# GRHV_Double_25v_KC_T.net
KiCad netlist of a schematic drawn in Altium Designer
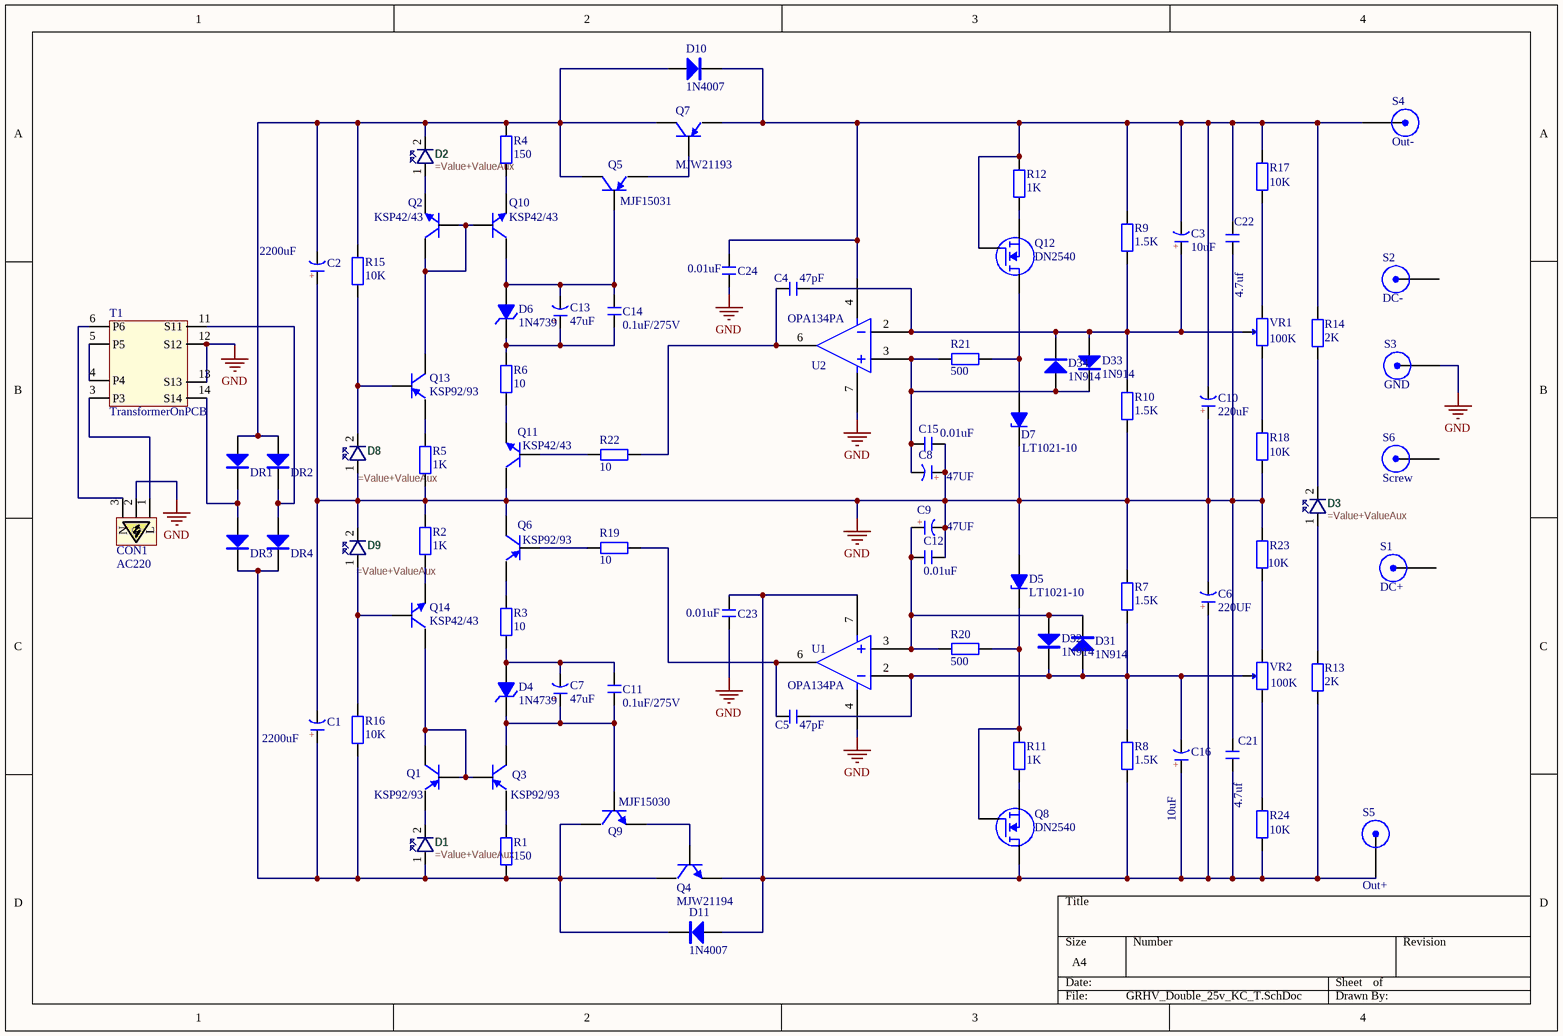
[diagram p0: GRHV_Double_25v_KC_T.SchDoc]

(export (version "E")
  (design (tool "Eeschema 10.0.6"))
  (components
    (comp (ref "C1")
      (value "2200uF")
      (footprint "CAP 11*35*60")
      (description "直插电解电容")
      (fields (field (name "版权归属") "源创客"))
      (libsource (lib "") (part "C-CAP_1"))
    )
    (comp (ref "C2")
      (value "2200uF")
      (footprint "CAP 11*35*60")
      (description "直插电解电容")
      (fields (field (name "版权归属") "源创客"))
      (libsource (lib "") (part "C-CAP_1"))
    )
    (comp (ref "C3")
      (value "10uF")
      (footprint "CAP 7.0*16.5*20")
      (description "直插电解电容")
      (fields (field (name "版权归属") "源创客"))
      (libsource (lib "") (part "C-CAP_1"))
    )
    (comp (ref "C4")
      (value "47pF")
      (footprint "CBB 6.3*6.3*5")
      (description "CBB电容")
      (fields (field (name "版权归属") "源创客"))
      (libsource (lib "电阻-电容-电感") (part "C-CBB"))
    )
    (comp (ref "C5")
      (value "47pF")
      (footprint "CBB 6.3*6.3*5")
      (description "CBB电容")
      (fields (field (name "版权归属") "源创客"))
      (libsource (lib "电阻-电容-电感") (part "C-CBB"))
    )
    (comp (ref "C6")
      (value "220UF")
      (footprint "CAP 7.0*16.5*20")
      (description "直插电解电容")
      (fields (field (name "版权归属") "源创客"))
      (libsource (lib "") (part "C-CAP_1"))
    )
    (comp (ref "C7")
      (value "47uF")
      (footprint "CAP 2.5*6.3*11.2")
      (description "直插电解电容")
      (fields (field (name "版权归属") "源创客"))
      (libsource (lib "") (part "C-CAP_1"))
    )
    (comp (ref "C8")
      (value "47UF")
      (footprint "CAP 2.5*6.3*11.2")
      (description "直插电解电容")
      (fields (field (name "版权归属") "源创客"))
      (libsource (lib "电阻-电容-电感") (part "C-CAP"))
    )
    (comp (ref "C9")
      (value "47UF")
      (footprint "CAP 2.5*6.3*11.2")
      (description "直插电解电容")
      (fields (field (name "版权归属") "源创客"))
      (libsource (lib "电阻-电容-电感") (part "C-CAP"))
    )
    (comp (ref "C10")
      (value "220uF")
      (footprint "CAP 7.0*16.5*20")
      (description "直插电解电容")
      (fields (field (name "版权归属") "源创客"))
      (libsource (lib "") (part "C-CAP_1"))
    )
    (comp (ref "C11")
      (value "0.1uF/275V")
      (footprint "CBB 6.3*6.3*5")
      (description "CBB电容")
      (fields (field (name "版权归属") "源创客"))
      (libsource (lib "电阻-电容-电感") (part "C-CBB"))
    )
    (comp (ref "C12")
      (value "0.01uF")
      (footprint "CBB 6.3*6.3*5")
      (description "CBB电容")
      (fields (field (name "版权归属") "源创客"))
      (libsource (lib "电阻-电容-电感") (part "C-CBB"))
    )
    (comp (ref "C13")
      (value "47uF")
      (footprint "CAP 2.5*6.3*11.2")
      (description "直插电解电容")
      (fields (field (name "版权归属") "源创客"))
      (libsource (lib "") (part "C-CAP_1"))
    )
    (comp (ref "C14")
      (value "0.1uF/275V")
      (footprint "CBB 6.3*6.3*5")
      (description "CBB电容")
      (fields (field (name "版权归属") "源创客"))
      (libsource (lib "电阻-电容-电感") (part "C-CBB"))
    )
    (comp (ref "C15")
      (value "0.01uF")
      (footprint "CBB 6.3*6.3*5")
      (description "CBB电容")
      (fields (field (name "版权归属") "源创客"))
      (libsource (lib "电阻-电容-电感") (part "C-CBB"))
    )
    (comp (ref "C16")
      (value "10uF")
      (footprint "CAP 7.0*16.5*20")
      (description "直插电解电容")
      (fields (field (name "版权归属") "源创客"))
      (libsource (lib "") (part "C-CAP_1"))
    )
    (comp (ref "C21")
      (value "4.7uf")
      (footprint "CBB 7.2*7.2*13")
      (description "MKS薄膜电容")
      (libsource (lib "电阻-电容-电感") (part "C-MKS"))
    )
    (comp (ref "C22")
      (value "4.7uf")
      (footprint "CBB 7.2*7.2*13")
      (description "MKS薄膜电容")
      (libsource (lib "电阻-电容-电感") (part "C-MKS"))
    )
    (comp (ref "C23")
      (value "0.01uF")
      (footprint "CBB 6.3*6.3*5")
      (description "CBB电容")
      (fields (field (name "版权归属") "源创客"))
      (libsource (lib "电阻-电容-电感") (part "C-CBB"))
    )
    (comp (ref "C24")
      (value "0.01uF")
      (footprint "CBB 6.3*6.3*5")
      (description "CBB电容")
      (fields (field (name "版权归属") "源创客"))
      (libsource (lib "电阻-电容-电感") (part "C-CBB"))
    )
    (comp (ref "CON1")
      (value "AC220")
      (footprint "HX5.08-3L")
      (libsource (lib "Connectors") (part "AC220-3"))
    )
    (comp (ref "D1")
      (value "~")
      (footprint "LED 3MM-R")
      (description "直插式LED")
      (libsource (lib "LED") (part "LED"))
    )
    (comp (ref "D2")
      (value "~")
      (footprint "LED 3MM-R")
      (description "直插式LED")
      (libsource (lib "LED") (part "LED"))
    )
    (comp (ref "D3")
      (value "~")
      (footprint "LED 3MM-R")
      (description "直插式LED")
      (libsource (lib "LED") (part "LED"))
    )
    (comp (ref "D4")
      (value "1N4739")
      (footprint "DO-41")
      (description "9.1V/1W稳压管")
      (libsource (lib "二极管-整流桥") (part "1N4739"))
    )
    (comp (ref "D5")
      (value "LT1021-10")
      (footprint "DIP8-300_MH")
      (description "10V Precision Reference 2 Pin Config")
      (libsource (lib "电压参考") (part "LT1021-10-2P"))
    )
    (comp (ref "D6")
      (value "1N4739")
      (footprint "DO-41")
      (description "9.1V/1W稳压管")
      (libsource (lib "二极管-整流桥") (part "1N4739"))
    )
    (comp (ref "D7")
      (value "LT1021-10")
      (footprint "DIP8-300_MH")
      (description "10V Precision Reference 2 Pin Config")
      (libsource (lib "电压参考") (part "LT1021-10-2P"))
    )
    (comp (ref "D8")
      (value "~")
      (footprint "LED 3MM-R")
      (description "直插式LED")
      (libsource (lib "LED") (part "LED"))
    )
    (comp (ref "D9")
      (value "~")
      (footprint "LED 3MM-R")
      (description "直插式LED")
      (libsource (lib "LED") (part "LED"))
    )
    (comp (ref "D10")
      (value "1N4007")
      (footprint "DO-41")
      (description "整流二极管")
      (fields (field (name "版权归属") "源创客"))
      (libsource (lib "二极管-整流桥") (part "1N4007"))
    )
    (comp (ref "D11")
      (value "1N4007")
      (footprint "DO-41")
      (description "整流二极管")
      (fields (field (name "版权归属") "源创客"))
      (libsource (lib "二极管-整流桥") (part "1N4007"))
    )
    (comp (ref "D31")
      (value "1N914")
      (footprint "DO-35")
      (description "高速开关管 1V/0.25W")
      (libsource (lib "二极管-整流桥") (part "1N914"))
    )
    (comp (ref "D32")
      (value "1N914")
      (footprint "DO-35")
      (description "高速开关管 1V/0.25W")
      (libsource (lib "二极管-整流桥") (part "1N914"))
    )
    (comp (ref "D33")
      (value "1N914")
      (footprint "DO-35")
      (description "高速开关管 1V/0.25W")
      (libsource (lib "二极管-整流桥") (part "1N914"))
    )
    (comp (ref "D34")
      (value "1N914")
      (footprint "DO-35")
      (description "高速开关管 1V/0.25W")
      (libsource (lib "二极管-整流桥") (part "1N914"))
    )
    (comp (ref "DR1")
      (value "VS-HFA08TB60-M3")
      (footprint "TO220AC")
      (description "Ultrafast Soft Recovery Diado 8A 600V")
      (libsource (lib "二极管-整流桥") (part "VS-HFA08TB60-M3"))
    )
    (comp (ref "DR2")
      (value "VS-HFA08TB60-M3")
      (footprint "TO220AC")
      (description "Ultrafast Soft Recovery Diado 8A 600V")
      (libsource (lib "二极管-整流桥") (part "VS-HFA08TB60-M3"))
    )
    (comp (ref "DR3")
      (value "VS-HFA08TB60-M3")
      (footprint "TO220AC")
      (description "Ultrafast Soft Recovery Diado 8A 600V")
      (libsource (lib "二极管-整流桥") (part "VS-HFA08TB60-M3"))
    )
    (comp (ref "DR4")
      (value "VS-HFA08TB60-M3")
      (footprint "TO220AC")
      (description "Ultrafast Soft Recovery Diado 8A 600V")
      (libsource (lib "二极管-整流桥") (part "VS-HFA08TB60-M3"))
    )
    (comp (ref "Q1")
      (value "KSP92/93")
      (footprint "TO92A")
      (description "High Voltage PNP Transistor")
      (libsource (lib "三极管") (part "KSP92/93"))
    )
    (comp (ref "Q2")
      (value "KSP42/43")
      (footprint "TO92A")
      (description "High Voltage NPN Transistor")
      (libsource (lib "三极管") (part "KSP42/43"))
    )
    (comp (ref "Q3")
      (value "KSP92/93")
      (footprint "TO92A")
      (description "High Voltage PNP Transistor")
      (libsource (lib "三极管") (part "KSP92/93"))
    )
    (comp (ref "Q4")
      (value "MJW21194")
      (footprint "TO247V-HeatSink")
      (description "Power NPN Transistor")
      (libsource (lib "三极管") (part "MJW21194"))
    )
    (comp (ref "Q5")
      (value "MJF15031")
      (footprint "TO220V")
      (description "Power PNP Transistor")
      (libsource (lib "三极管") (part "MJF15031"))
    )
    (comp (ref "Q6")
      (value "KSP92/93")
      (footprint "TO92A")
      (description "High Voltage PNP Transistor")
      (libsource (lib "三极管") (part "KSP92/93"))
    )
    (comp (ref "Q7")
      (value "MJW21193")
      (footprint "TO247V-HeatSink")
      (description "Power PNP Transistor")
      (libsource (lib "三极管") (part "MJW21193"))
    )
    (comp (ref "Q8")
      (value "DN2540")
      (footprint "TO92A")
      (description "N沟道耗尽型DMOS场效应管 400V/150ma")
      (libsource (lib "场效应管") (part "DN2540"))
    )
    (comp (ref "Q9")
      (value "MJF15030")
      (footprint "TO220V")
      (description "Power NPN Transistor")
      (libsource (lib "三极管") (part "MJF15030"))
    )
    (comp (ref "Q10")
      (value "KSP42/43")
      (footprint "TO92A")
      (description "High Voltage NPN Transistor")
      (libsource (lib "三极管") (part "KSP42/43"))
    )
    (comp (ref "Q11")
      (value "KSP42/43")
      (footprint "TO92A")
      (description "High Voltage NPN Transistor")
      (libsource (lib "三极管") (part "KSP42/43"))
    )
    (comp (ref "Q12")
      (value "DN2540")
      (footprint "TO92A")
      (description "N沟道耗尽型DMOS场效应管 400V/150ma")
      (libsource (lib "场效应管") (part "DN2540"))
    )
    (comp (ref "Q13")
      (value "KSP92/93")
      (footprint "TO92A")
      (description "High Voltage PNP Transistor")
      (libsource (lib "三极管") (part "KSP92/93"))
    )
    (comp (ref "Q14")
      (value "KSP42/43")
      (footprint "TO92A")
      (description "High Voltage NPN Transistor")
      (libsource (lib "三极管") (part "KSP42/43"))
    )
    (comp (ref "R1")
      (value "150")
      (footprint "RS 1/4W")
      (description "直插色环电阻")
      (fields (field (name "版权归属") "源创客"))
      (libsource (lib "电阻-电容-电感") (part "R-CRR"))
    )
    (comp (ref "R2")
      (value "1K")
      (footprint "RS 1/4W")
      (description "直插色环电阻")
      (fields (field (name "版权归属") "源创客"))
      (libsource (lib "电阻-电容-电感") (part "R-CRR"))
    )
    (comp (ref "R3")
      (value "10")
      (footprint "RS 1/4W")
      (description "直插色环电阻")
      (fields (field (name "版权归属") "源创客"))
      (libsource (lib "电阻-电容-电感") (part "R-CRR"))
    )
    (comp (ref "R4")
      (value "150")
      (footprint "RS 1/4W")
      (description "直插色环电阻")
      (fields (field (name "版权归属") "源创客"))
      (libsource (lib "电阻-电容-电感") (part "R-CRR"))
    )
    (comp (ref "R5")
      (value "1K")
      (footprint "RS 1/4W")
      (description "直插色环电阻")
      (fields (field (name "版权归属") "源创客"))
      (libsource (lib "电阻-电容-电感") (part "R-CRR"))
    )
    (comp (ref "R6")
      (value "10")
      (footprint "RS 1/4W")
      (description "直插色环电阻")
      (fields (field (name "版权归属") "源创客"))
      (libsource (lib "电阻-电容-电感") (part "R-CRR"))
    )
    (comp (ref "R7")
      (value "1.5K")
      (footprint "RS 1/4W")
      (description "直插色环电阻")
      (fields (field (name "版权归属") "源创客"))
      (libsource (lib "电阻-电容-电感") (part "R-CRR"))
    )
    (comp (ref "R8")
      (value "1.5K")
      (footprint "RS 1/4W")
      (description "直插色环电阻")
      (fields (field (name "版权归属") "源创客"))
      (libsource (lib "电阻-电容-电感") (part "R-CRR"))
    )
    (comp (ref "R9")
      (value "1.5K")
      (footprint "RS 1/4W")
      (description "直插色环电阻")
      (fields (field (name "版权归属") "源创客"))
      (libsource (lib "电阻-电容-电感") (part "R-CRR"))
    )
    (comp (ref "R10")
      (value "1.5K")
      (footprint "RS 1/4W")
      (description "直插色环电阻")
      (fields (field (name "版权归属") "源创客"))
      (libsource (lib "电阻-电容-电感") (part "R-CRR"))
    )
    (comp (ref "R11")
      (value "1K")
      (footprint "RS 1/4W-V3")
      (description "直插色环电阻")
      (fields (field (name "版权归属") "源创客"))
      (libsource (lib "电阻-电容-电感") (part "R-CRR"))
    )
    (comp (ref "R12")
      (value "1K")
      (footprint "RS 1/4W-V3")
      (description "直插色环电阻")
      (fields (field (name "版权归属") "源创客"))
      (libsource (lib "电阻-电容-电感") (part "R-CRR"))
    )
    (comp (ref "R13")
      (value "2K")
      (footprint "RS 1/4W")
      (description "直插色环电阻")
      (fields (field (name "版权归属") "源创客"))
      (libsource (lib "电阻-电容-电感") (part "R-CRR"))
    )
    (comp (ref "R14")
      (value "2K")
      (footprint "RS 1/4W")
      (description "直插色环电阻")
      (fields (field (name "版权归属") "源创客"))
      (libsource (lib "电阻-电容-电感") (part "R-CRR"))
    )
    (comp (ref "R15")
      (value "10K")
      (footprint "RS 1/4W")
      (description "直插色环电阻")
      (fields (field (name "版权归属") "源创客"))
      (libsource (lib "电阻-电容-电感") (part "R-CRR"))
    )
    (comp (ref "R16")
      (value "10K")
      (footprint "RS 1/4W")
      (description "直插色环电阻")
      (fields (field (name "版权归属") "源创客"))
      (libsource (lib "电阻-电容-电感") (part "R-CRR"))
    )
    (comp (ref "R17")
      (value "10K")
      (footprint "RS 1/4W-V3")
      (description "直插色环电阻")
      (fields (field (name "版权归属") "源创客"))
      (libsource (lib "电阻-电容-电感") (part "R-CRR"))
    )
    (comp (ref "R18")
      (value "10K")
      (footprint "RS 1/4W")
      (description "直插色环电阻")
      (fields (field (name "版权归属") "源创客"))
      (libsource (lib "电阻-电容-电感") (part "R-CRR"))
    )
    (comp (ref "R19")
      (value "10")
      (footprint "RS 1/4W")
      (description "直插色环电阻")
      (fields (field (name "版权归属") "源创客"))
      (libsource (lib "电阻-电容-电感") (part "R-CRR"))
    )
    (comp (ref "R20")
      (value "500")
      (footprint "RS 1/4W-V3")
      (description "直插色环电阻")
      (fields (field (name "版权归属") "源创客"))
      (libsource (lib "电阻-电容-电感") (part "R-CRR"))
    )
    (comp (ref "R21")
      (value "500")
      (footprint "RS 1/4W-V3")
      (description "直插色环电阻")
      (fields (field (name "版权归属") "源创客"))
      (libsource (lib "电阻-电容-电感") (part "R-CRR"))
    )
    (comp (ref "R22")
      (value "10")
      (footprint "RS 1/4W")
      (description "直插色环电阻")
      (fields (field (name "版权归属") "源创客"))
      (libsource (lib "电阻-电容-电感") (part "R-CRR"))
    )
    (comp (ref "R23")
      (value "10K")
      (footprint "RS 1/4W")
      (description "直插色环电阻")
      (fields (field (name "版权归属") "源创客"))
      (libsource (lib "电阻-电容-电感") (part "R-CRR"))
    )
    (comp (ref "R24")
      (value "10K")
      (footprint "RS 1/4W-V3")
      (description "直插色环电阻")
      (fields (field (name "版权归属") "源创客"))
      (libsource (lib "电阻-电容-电感") (part "R-CRR"))
    )
    (comp (ref "S1")
      (value "DC+")
      (footprint "Screw-M3")
      (description "Screw Connector")
      (libsource (lib "Connectors") (part "ScrewConnector"))
    )
    (comp (ref "S2")
      (value "DC-")
      (footprint "Screw-M3")
      (description "Screw Connector")
      (libsource (lib "Connectors") (part "ScrewConnector"))
    )
    (comp (ref "S3")
      (value "GND")
      (footprint "Screw-M4-Small")
      (description "Screw Connector")
      (libsource (lib "Connectors") (part "ScrewConnector"))
    )
    (comp (ref "S4")
      (value "Out-")
      (footprint "Screw-M4-Small")
      (description "Screw Connector")
      (libsource (lib "Connectors") (part "ScrewConnector"))
    )
    (comp (ref "S5")
      (value "Out+")
      (footprint "Screw-M4-Small")
      (description "Screw Connector")
      (libsource (lib "Connectors") (part "ScrewConnector"))
    )
    (comp (ref "S6")
      (value "Screw")
      (footprint "Screw-M3")
      (description "Screw Connector")
      (libsource (lib "Connectors") (part "ScrewConnector"))
    )
    (comp (ref "T1")
      (value "TransformerOnPCB")
      (footprint "TalemaTransformer25W")
      (description "Talema On Board Transformer 25W")
      (libsource (lib "KC_amp") (part "TransformerOnPCB"))
    )
    (comp (ref "U1") (value "OPA134PA") (footprint "DIP8-300_MH") (libsource (lib "运放") (part "OPA134PA")))
    (comp (ref "U2") (value "OPA134PA") (footprint "DIP8-300_MH") (libsource (lib "运放") (part "OPA134PA")))
    (comp (ref "VR1")
      (value "100K")
      (footprint "RS 1/2W-VR")
      (description "直插可调电阻-顶调")
      (fields (field (name "Comment") "VR-W"))
      (libsource (lib "电阻-电容-电感") (part "VR-W"))
    )
    (comp (ref "VR2")
      (value "100K")
      (footprint "RS 1/2W-VR")
      (description "直插可调电阻-顶调")
      (fields (field (name "Comment") "VR-W"))
      (libsource (lib "电阻-电容-电感") (part "VR-W"))
    )
  )
  (nets
    (net (code "1") (name "GND") (class "Default")
      (node (ref "C1") (pin "2") (pinfunction "K_2") (pintype "passive"))
      (node (ref "C10") (pin "1") (pinfunction "A_1") (pintype "passive"))
      (node (ref "C12") (pin "2") (pinfunction "2_2") (pintype "passive"))
      (node (ref "C15") (pin "2") (pinfunction "2_2") (pintype "passive"))
      (node (ref "C2") (pin "1") (pinfunction "A_1") (pintype "passive"))
      (node (ref "C21") (pin "2") (pinfunction "2_2") (pintype "passive"))
      (node (ref "C22") (pin "1") (pinfunction "1_1") (pintype "passive"))
      (node (ref "C23") (pin "1") (pinfunction "1_1") (pintype "passive"))
      (node (ref "C24") (pin "1") (pinfunction "1_1") (pintype "passive"))
      (node (ref "C6") (pin "2") (pinfunction "K_2") (pintype "passive"))
      (node (ref "C8") (pin "1") (pinfunction "A_1") (pintype "passive"))
      (node (ref "C9") (pin "2") (pinfunction "K_2") (pintype "passive"))
      (node (ref "CON1") (pin "2") (pinfunction "G_2") (pintype "passive"))
      (node (ref "D5") (pin "4") (pinfunction "A_4") (pintype "passive"))
      (node (ref "D7") (pin "6") (pinfunction "K_6") (pintype "passive"))
      (node (ref "D8") (pin "1") (pinfunction "A_1") (pintype "passive"))
      (node (ref "D9") (pin "2") (pinfunction "K_2") (pintype "passive"))
      (node (ref "Q11") (pin "3") (pinfunction "C_3") (pintype "passive"))
      (node (ref "Q6") (pin "3") (pinfunction "C_3") (pintype "passive"))
      (node (ref "R10") (pin "1") (pinfunction "1_1") (pintype "passive"))
      (node (ref "R18") (pin "1") (pinfunction "1_1") (pintype "passive"))
      (node (ref "R2") (pin "2") (pinfunction "2_2") (pintype "passive"))
      (node (ref "R23") (pin "2") (pinfunction "2_2") (pintype "passive"))
      (node (ref "R5") (pin "1") (pinfunction "1_1") (pintype "passive"))
      (node (ref "R7") (pin "2") (pinfunction "2_2") (pintype "passive"))
      (node (ref "S3") (pin "1") (pinfunction "X_1") (pintype "passive"))
      (node (ref "T1") (pin "12") (pinfunction "S12_12") (pintype "passive"))
      (node (ref "T1") (pin "13") (pinfunction "S13_13") (pintype "passive"))
      (node (ref "U1") (pin "4") (pinfunction "V-_4") (pintype "passive"))
      (node (ref "U2") (pin "7") (pinfunction "V+_7") (pintype "passive"))
    )
    (net (code "2") (name "Net-(C1-A)") (class "Default")
      (node (ref "C1") (pin "1") (pinfunction "A_1") (pintype "passive"))
      (node (ref "D1") (pin "1") (pinfunction "A_1") (pintype "passive"))
      (node (ref "D11") (pin "2") (pinfunction "K_2") (pintype "passive"))
      (node (ref "DR3") (pin "1") (pinfunction "Cathode_1") (pintype "passive"))
      (node (ref "DR4") (pin "1") (pinfunction "Cathode_1") (pintype "passive"))
      (node (ref "Q4") (pin "2") (pinfunction "C_2") (pintype "passive"))
      (node (ref "Q9") (pin "2") (pinfunction "C_2") (pintype "passive"))
      (node (ref "R1") (pin "1") (pinfunction "1_1") (pintype "passive"))
      (node (ref "R16") (pin "1") (pinfunction "1_1") (pintype "passive"))
    )
    (net (code "3") (name "Net-(C2-K)") (class "Default")
      (node (ref "C2") (pin "2") (pinfunction "K_2") (pintype "passive"))
      (node (ref "D10") (pin "1") (pinfunction "A_1") (pintype "passive"))
      (node (ref "D2") (pin "2") (pinfunction "K_2") (pintype "passive"))
      (node (ref "DR1") (pin "2") (pinfunction "Anode_2") (pintype "passive"))
      (node (ref "DR2") (pin "2") (pinfunction "Anode_2") (pintype "passive"))
      (node (ref "Q5") (pin "2") (pinfunction "C_2") (pintype "passive"))
      (node (ref "Q7") (pin "2") (pinfunction "C_2") (pintype "passive"))
      (node (ref "R15") (pin "2") (pinfunction "2_2") (pintype "passive"))
      (node (ref "R4") (pin "2") (pinfunction "2_2") (pintype "passive"))
    )
    (net (code "4") (name "Net-(C3-A)") (class "Default")
      (node (ref "C3") (pin "1") (pinfunction "A_1") (pintype "passive"))
      (node (ref "C4") (pin "2") (pinfunction "2_2") (pintype "passive"))
      (node (ref "D33") (pin "1") (pinfunction "A_1") (pintype "passive"))
      (node (ref "D34") (pin "2") (pinfunction "K_2") (pintype "passive"))
      (node (ref "R10") (pin "2") (pinfunction "2_2") (pintype "passive"))
      (node (ref "R9") (pin "1") (pinfunction "1_1") (pintype "passive"))
      (node (ref "U2") (pin "2") (pinfunction "-in_2") (pintype "passive"))
      (node (ref "VR1") (pin "3") (pinfunction "3_3") (pintype "passive"))
    )
    (net (code "5") (name "Net-(C7-A)") (class "Default")
      (node (ref "C11") (pin "1") (pinfunction "1_1") (pintype "passive"))
      (node (ref "C7") (pin "1") (pinfunction "A_1") (pintype "passive"))
      (node (ref "D4") (pin "2") (pinfunction "K_2") (pintype "passive"))
      (node (ref "Q3") (pin "3") (pinfunction "C_3") (pintype "passive"))
      (node (ref "Q9") (pin "1") (pinfunction "B_1") (pintype "passive"))
    )
    (net (code "6") (name "Net-(C7-K)") (class "Default")
      (node (ref "C11") (pin "2") (pinfunction "2_2") (pintype "passive"))
      (node (ref "C7") (pin "2") (pinfunction "K_2") (pintype "passive"))
      (node (ref "D4") (pin "1") (pinfunction "A_1") (pintype "passive"))
      (node (ref "R3") (pin "1") (pinfunction "1_1") (pintype "passive"))
    )
    (net (code "7") (name "Net-(C8-K)") (class "Default")
      (node (ref "C15") (pin "1") (pinfunction "1_1") (pintype "passive"))
      (node (ref "C8") (pin "2") (pinfunction "K_2") (pintype "passive"))
      (node (ref "D33") (pin "2") (pinfunction "K_2") (pintype "passive"))
      (node (ref "D34") (pin "1") (pinfunction "A_1") (pintype "passive"))
      (node (ref "R21") (pin "1") (pinfunction "1_1") (pintype "passive"))
      (node (ref "U2") (pin "3") (pinfunction "+in_3") (pintype "passive"))
    )
    (net (code "8") (name "Net-(C9-A)") (class "Default")
      (node (ref "C12") (pin "1") (pinfunction "1_1") (pintype "passive"))
      (node (ref "C9") (pin "1") (pinfunction "A_1") (pintype "passive"))
      (node (ref "D31") (pin "2") (pinfunction "K_2") (pintype "passive"))
      (node (ref "D32") (pin "1") (pinfunction "A_1") (pintype "passive"))
      (node (ref "R20") (pin "1") (pinfunction "1_1") (pintype "passive"))
      (node (ref "U1") (pin "3") (pinfunction "+in_3") (pintype "passive"))
    )
    (net (code "9") (name "Net-(C10-K)") (class "Default")
      (node (ref "C10") (pin "2") (pinfunction "K_2") (pintype "passive"))
      (node (ref "C22") (pin "2") (pinfunction "2_2") (pintype "passive"))
      (node (ref "C24") (pin "2") (pinfunction "2_2") (pintype "passive"))
      (node (ref "C3") (pin "2") (pinfunction "K_2") (pintype "passive"))
      (node (ref "D10") (pin "2") (pinfunction "K_2") (pintype "passive"))
      (node (ref "Q12") (pin "2") (pinfunction "G_2") (pintype "passive"))
      (node (ref "Q7") (pin "3") (pinfunction "E_3") (pintype "passive"))
      (node (ref "R12") (pin "2") (pinfunction "2_2") (pintype "passive"))
      (node (ref "R14") (pin "2") (pinfunction "2_2") (pintype "passive"))
      (node (ref "R17") (pin "2") (pinfunction "2_2") (pintype "passive"))
      (node (ref "R9") (pin "2") (pinfunction "2_2") (pintype "passive"))
      (node (ref "S4") (pin "1") (pinfunction "X_1") (pintype "passive"))
      (node (ref "U2") (pin "4") (pinfunction "V-_4") (pintype "passive"))
    )
    (net (code "10") (name "Net-(C13-A)") (class "Default")
      (node (ref "C13") (pin "1") (pinfunction "A_1") (pintype "passive"))
      (node (ref "C14") (pin "1") (pinfunction "1_1") (pintype "passive"))
      (node (ref "D6") (pin "2") (pinfunction "K_2") (pintype "passive"))
      (node (ref "R6") (pin "2") (pinfunction "2_2") (pintype "passive"))
    )
    (net (code "11") (name "Net-(C13-K)") (class "Default")
      (node (ref "C13") (pin "2") (pinfunction "K_2") (pintype "passive"))
      (node (ref "C14") (pin "2") (pinfunction "2_2") (pintype "passive"))
      (node (ref "D6") (pin "1") (pinfunction "A_1") (pintype "passive"))
      (node (ref "Q10") (pin "3") (pinfunction "C_3") (pintype "passive"))
      (node (ref "Q5") (pin "1") (pinfunction "B_1") (pintype "passive"))
    )
    (net (code "12") (name "Net-(C16-A)") (class "Default")
      (node (ref "C16") (pin "1") (pinfunction "A_1") (pintype "passive"))
      (node (ref "C21") (pin "1") (pinfunction "1_1") (pintype "passive"))
      (node (ref "C23") (pin "2") (pinfunction "2_2") (pintype "passive"))
      (node (ref "C6") (pin "1") (pinfunction "A_1") (pintype "passive"))
      (node (ref "D11") (pin "1") (pinfunction "A_1") (pintype "passive"))
      (node (ref "Q4") (pin "3") (pinfunction "E_3") (pintype "passive"))
      (node (ref "Q8") (pin "3") (pinfunction "D_3") (pintype "passive"))
      (node (ref "R13") (pin "2") (pinfunction "2_2") (pintype "passive"))
      (node (ref "R24") (pin "1") (pinfunction "1_1") (pintype "passive"))
      (node (ref "R8") (pin "1") (pinfunction "1_1") (pintype "passive"))
      (node (ref "S5") (pin "1") (pinfunction "X_1") (pintype "passive"))
      (node (ref "U1") (pin "7") (pinfunction "V+_7") (pintype "passive"))
    )
    (net (code "13") (name "Net-(C16-K)") (class "Default")
      (node (ref "C16") (pin "2") (pinfunction "K_2") (pintype "passive"))
      (node (ref "C5") (pin "2") (pinfunction "2_2") (pintype "passive"))
      (node (ref "D31") (pin "1") (pinfunction "A_1") (pintype "passive"))
      (node (ref "D32") (pin "2") (pinfunction "K_2") (pintype "passive"))
      (node (ref "R7") (pin "1") (pinfunction "1_1") (pintype "passive"))
      (node (ref "R8") (pin "2") (pinfunction "2_2") (pintype "passive"))
      (node (ref "U1") (pin "2") (pinfunction "-in_2") (pintype "passive"))
      (node (ref "VR2") (pin "3") (pinfunction "3_3") (pintype "passive"))
    )
    (net (code "14") (name "Net-(CON1-L)") (class "Default")
      (node (ref "CON1") (pin "1") (pinfunction "L_1") (pintype "passive"))
      (node (ref "T1") (pin "3") (pinfunction "P3_3") (pintype "passive"))
    )
    (net (code "15") (name "Net-(CON1-N)") (class "Default")
      (node (ref "CON1") (pin "3") (pinfunction "N_3") (pintype "passive"))
      (node (ref "T1") (pin "6") (pinfunction "P6_6") (pintype "passive"))
    )
    (net (code "16") (name "Net-(D1-K)") (class "Default")
      (node (ref "D1") (pin "2") (pinfunction "K_2") (pintype "passive"))
      (node (ref "Q1") (pin "1") (pinfunction "E_1") (pintype "passive"))
    )
    (net (code "17") (name "Net-(D2-A)") (class "Default")
      (node (ref "D2") (pin "1") (pinfunction "A_1") (pintype "passive"))
      (node (ref "Q2") (pin "1") (pinfunction "E_1") (pintype "passive"))
    )
    (net (code "18") (name "Net-(D3-A)") (class "Default")
      (node (ref "D3") (pin "1") (pinfunction "A_1") (pintype "passive"))
      (node (ref "R13") (pin "1") (pinfunction "1_1") (pintype "passive"))
    )
    (net (code "19") (name "Net-(D3-K)") (class "Default")
      (node (ref "D3") (pin "2") (pinfunction "K_2") (pintype "passive"))
      (node (ref "R14") (pin "1") (pinfunction "1_1") (pintype "passive"))
    )
    (net (code "20") (name "Net-(D5-K)") (class "Default")
      (node (ref "D5") (pin "6") (pinfunction "K_6") (pintype "passive"))
      (node (ref "Q8") (pin "2") (pinfunction "G_2") (pintype "passive"))
      (node (ref "R11") (pin "2") (pinfunction "2_2") (pintype "passive"))
      (node (ref "R20") (pin "2") (pinfunction "2_2") (pintype "passive"))
    )
    (net (code "21") (name "Net-(D7-A)") (class "Default")
      (node (ref "D7") (pin "4") (pinfunction "A_4") (pintype "passive"))
      (node (ref "Q12") (pin "3") (pinfunction "D_3") (pintype "passive"))
      (node (ref "R21") (pin "2") (pinfunction "2_2") (pintype "passive"))
    )
    (net (code "22") (name "Net-(D8-K)") (class "Default")
      (node (ref "D8") (pin "2") (pinfunction "K_2") (pintype "passive"))
      (node (ref "Q13") (pin "2") (pinfunction "B_2") (pintype "passive"))
      (node (ref "R15") (pin "1") (pinfunction "1_1") (pintype "passive"))
    )
    (net (code "23") (name "Net-(D9-A)") (class "Default")
      (node (ref "D9") (pin "1") (pinfunction "A_1") (pintype "passive"))
      (node (ref "Q14") (pin "2") (pinfunction "B_2") (pintype "passive"))
      (node (ref "R16") (pin "2") (pinfunction "2_2") (pintype "passive"))
    )
    (net (code "24") (name "Net-(DR1-Cathode)") (class "Default")
      (node (ref "DR1") (pin "1") (pinfunction "Cathode_1") (pintype "passive"))
      (node (ref "DR3") (pin "2") (pinfunction "Anode_2") (pintype "passive"))
      (node (ref "T1") (pin "14") (pinfunction "S14_14") (pintype "passive"))
    )
    (net (code "25") (name "Net-(DR2-Cathode)") (class "Default")
      (node (ref "DR2") (pin "1") (pinfunction "Cathode_1") (pintype "passive"))
      (node (ref "DR4") (pin "2") (pinfunction "Anode_2") (pintype "passive"))
      (node (ref "T1") (pin "11") (pinfunction "S11_11") (pintype "passive"))
    )
    (net (code "26") (name "Net-(Q1-B)") (class "Default")
      (node (ref "Q1") (pin "2") (pinfunction "B_2") (pintype "passive"))
      (node (ref "Q1") (pin "3") (pinfunction "C_3") (pintype "passive"))
      (node (ref "Q14") (pin "3") (pinfunction "C_3") (pintype "passive"))
      (node (ref "Q3") (pin "2") (pinfunction "B_2") (pintype "passive"))
    )
    (net (code "27") (name "Net-(Q3-E)") (class "Default")
      (node (ref "Q3") (pin "1") (pinfunction "E_1") (pintype "passive"))
      (node (ref "R1") (pin "2") (pinfunction "2_2") (pintype "passive"))
    )
    (net (code "28") (name "Net-(Q4-B)") (class "Default")
      (node (ref "Q4") (pin "1") (pinfunction "B_1") (pintype "passive"))
      (node (ref "Q9") (pin "3") (pinfunction "E_3") (pintype "passive"))
    )
    (net (code "29") (name "Net-(Q5-E)") (class "Default")
      (node (ref "Q5") (pin "3") (pinfunction "E_3") (pintype "passive"))
      (node (ref "Q7") (pin "1") (pinfunction "B_1") (pintype "passive"))
    )
    (net (code "30") (name "Net-(Q6-B)") (class "Default")
      (node (ref "Q6") (pin "2") (pinfunction "B_2") (pintype "passive"))
      (node (ref "R19") (pin "1") (pinfunction "1_1") (pintype "passive"))
    )
    (net (code "31") (name "Net-(Q6-E)") (class "Default")
      (node (ref "Q6") (pin "1") (pinfunction "E_1") (pintype "passive"))
      (node (ref "R3") (pin "2") (pinfunction "2_2") (pintype "passive"))
    )
    (net (code "32") (name "Net-(Q8-S)") (class "Default")
      (node (ref "Q8") (pin "1") (pinfunction "S_1") (pintype "passive"))
      (node (ref "R11") (pin "1") (pinfunction "1_1") (pintype "passive"))
    )
    (net (code "33") (name "Net-(Q10-B)") (class "Default")
      (node (ref "Q10") (pin "2") (pinfunction "B_2") (pintype "passive"))
      (node (ref "Q13") (pin "3") (pinfunction "C_3") (pintype "passive"))
      (node (ref "Q2") (pin "2") (pinfunction "B_2") (pintype "passive"))
      (node (ref "Q2") (pin "3") (pinfunction "C_3") (pintype "passive"))
    )
    (net (code "34") (name "Net-(Q10-E)") (class "Default")
      (node (ref "Q10") (pin "1") (pinfunction "E_1") (pintype "passive"))
      (node (ref "R4") (pin "1") (pinfunction "1_1") (pintype "passive"))
    )
    (net (code "35") (name "Net-(Q11-B)") (class "Default")
      (node (ref "Q11") (pin "2") (pinfunction "B_2") (pintype "passive"))
      (node (ref "R22") (pin "1") (pinfunction "1_1") (pintype "passive"))
    )
    (net (code "36") (name "Net-(Q11-E)") (class "Default")
      (node (ref "Q11") (pin "1") (pinfunction "E_1") (pintype "passive"))
      (node (ref "R6") (pin "1") (pinfunction "1_1") (pintype "passive"))
    )
    (net (code "37") (name "Net-(Q12-S)") (class "Default")
      (node (ref "Q12") (pin "1") (pinfunction "S_1") (pintype "passive"))
      (node (ref "R12") (pin "1") (pinfunction "1_1") (pintype "passive"))
    )
    (net (code "38") (name "Net-(Q13-E)") (class "Default")
      (node (ref "Q13") (pin "1") (pinfunction "E_1") (pintype "passive"))
      (node (ref "R5") (pin "2") (pinfunction "2_2") (pintype "passive"))
    )
    (net (code "39") (name "Net-(Q14-E)") (class "Default")
      (node (ref "Q14") (pin "1") (pinfunction "E_1") (pintype "passive"))
      (node (ref "R2") (pin "1") (pinfunction "1_1") (pintype "passive"))
    )
    (net (code "40") (name "Net-(R17-Pad1)") (class "Default")
      (node (ref "R17") (pin "1") (pinfunction "1_1") (pintype "passive"))
      (node (ref "VR1") (pin "2") (pinfunction "2_2") (pintype "passive"))
    )
    (net (code "41") (name "Net-(R18-Pad2)") (class "Default")
      (node (ref "R18") (pin "2") (pinfunction "2_2") (pintype "passive"))
      (node (ref "VR1") (pin "1") (pinfunction "1_1") (pintype "passive"))
    )
    (net (code "42") (name "Net-(R23-Pad1)") (class "Default")
      (node (ref "R23") (pin "1") (pinfunction "1_1") (pintype "passive"))
      (node (ref "VR2") (pin "2") (pinfunction "2_2") (pintype "passive"))
    )
    (net (code "43") (name "Net-(R24-Pad2)") (class "Default")
      (node (ref "R24") (pin "2") (pinfunction "2_2") (pintype "passive"))
      (node (ref "VR2") (pin "1") (pinfunction "1_1") (pintype "passive"))
    )
    (net (code "44") (name "Net-(T1-P4)") (class "Default")
      (node (ref "T1") (pin "4") (pinfunction "P4_4") (pintype "passive"))
      (node (ref "T1") (pin "5") (pinfunction "P5_5") (pintype "passive"))
    )
    (net (code "45") (name "Net-(U1-out)") (class "Default")
      (node (ref "C5") (pin "1") (pinfunction "1_1") (pintype "passive"))
      (node (ref "R19") (pin "2") (pinfunction "2_2") (pintype "passive"))
      (node (ref "U1") (pin "6") (pinfunction "out_6") (pintype "passive"))
    )
    (net (code "46") (name "Net-(U2-out)") (class "Default")
      (node (ref "C4") (pin "1") (pinfunction "1_1") (pintype "passive"))
      (node (ref "R22") (pin "2") (pinfunction "2_2") (pintype "passive"))
      (node (ref "U2") (pin "6") (pinfunction "out_6") (pintype "passive"))
    )
    (net (code "47") (name "unconnected-(S1-X-Pad1)") (class "Default")
      (node (ref "S1") (pin "1") (pinfunction "X_1") (pintype "passive"))
    )
    (net (code "48") (name "unconnected-(S2-X-Pad1)") (class "Default")
      (node (ref "S2") (pin "1") (pinfunction "X_1") (pintype "passive"))
    )
    (net (code "49") (name "unconnected-(S6-X-Pad1)") (class "Default")
      (node (ref "S6") (pin "1") (pinfunction "X_1") (pintype "passive"))
    )
  )
)
